# V1_DIL.net
KiCad netlist of a schematic drawn in EAGLE
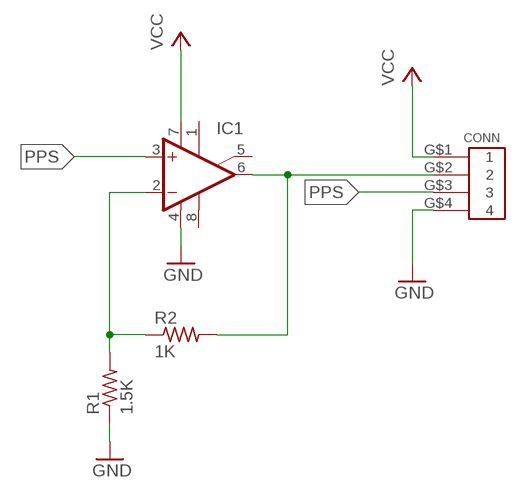
[diagram p0: schematic, sheet 1]

(export (version "E")
  (design (tool "Eeschema 10.0.6"))
  (components
    (comp (ref "CONN")
      (value "OSTVN04A150")
      (footprint "eagle-import:OSTVN04A150")
      (libsource (lib "eagle-import") (part "OSTVN04A150"))
    )
    (comp (ref "IC1")
      (value "LM741P")
      (footprint "eagle-import:DIL08")
      (libsource (lib "eagle-import") (part "741PLM"))
    )
    (comp (ref "R1")
      (value "1.5K")
      (footprint "eagle-import:0204_7")
      (libsource (lib "eagle-import") (part "R-US_0204/7"))
    )
    (comp (ref "R2")
      (value "1K")
      (footprint "eagle-import:0204_7")
      (libsource (lib "eagle-import") (part "R-US_0204/7"))
    )
  )
  (nets
    (net (code "1") (name "GND") (class "Default")
      (node (ref "CONN") (pin "G$4") (pinfunction "4_G$4") (pintype "bidirectional"))
      (node (ref "IC1") (pin "4") (pinfunction "V-_4") (pintype "power_in"))
      (node (ref "R1") (pin "1") (pinfunction "1_1") (pintype "passive"))
    )
    (net (code "2") (name "Net-(CONN-2)") (class "Default")
      (node (ref "CONN") (pin "G$2") (pinfunction "2_G$2") (pintype "bidirectional"))
      (node (ref "IC1") (pin "6") (pinfunction "OUT_6") (pintype "output"))
      (node (ref "R2") (pin "2") (pinfunction "2_2") (pintype "passive"))
    )
    (net (code "3") (name "Net-(IC1--IN)") (class "Default")
      (node (ref "IC1") (pin "2") (pinfunction "-IN_2") (pintype "input"))
      (node (ref "R1") (pin "2") (pinfunction "2_2") (pintype "passive"))
      (node (ref "R2") (pin "1") (pinfunction "1_1") (pintype "passive"))
    )
    (net (code "4") (name "PPS") (class "Default")
      (node (ref "CONN") (pin "G$3") (pinfunction "3_G$3") (pintype "bidirectional"))
      (node (ref "IC1") (pin "3") (pinfunction "+IN_3") (pintype "input"))
    )
    (net (code "5") (name "VCC") (class "Default")
      (node (ref "CONN") (pin "G$1") (pinfunction "1_G$1") (pintype "bidirectional"))
      (node (ref "IC1") (pin "7") (pinfunction "V+_7") (pintype "power_in"))
    )
    (net (code "6") (name "unconnected-(IC1-ON1-Pad1)") (class "Default")
      (node (ref "IC1") (pin "1") (pinfunction "ON1_1") (pintype "passive"))
    )
    (net (code "7") (name "unconnected-(IC1-ON2-Pad5)") (class "Default")
      (node (ref "IC1") (pin "5") (pinfunction "ON2_5") (pintype "passive"))
    )
    (net (code "8") (name "unconnected-(IC1-OPT-Pad8)") (class "Default")
      (node (ref "IC1") (pin "8") (pinfunction "OPT_8") (pintype "passive"))
    )
  )
)
